# pioneer_2-bluepill_eletronic_wrapper-sup.net
KiCad netlist of a schematic drawn in Altium Designer
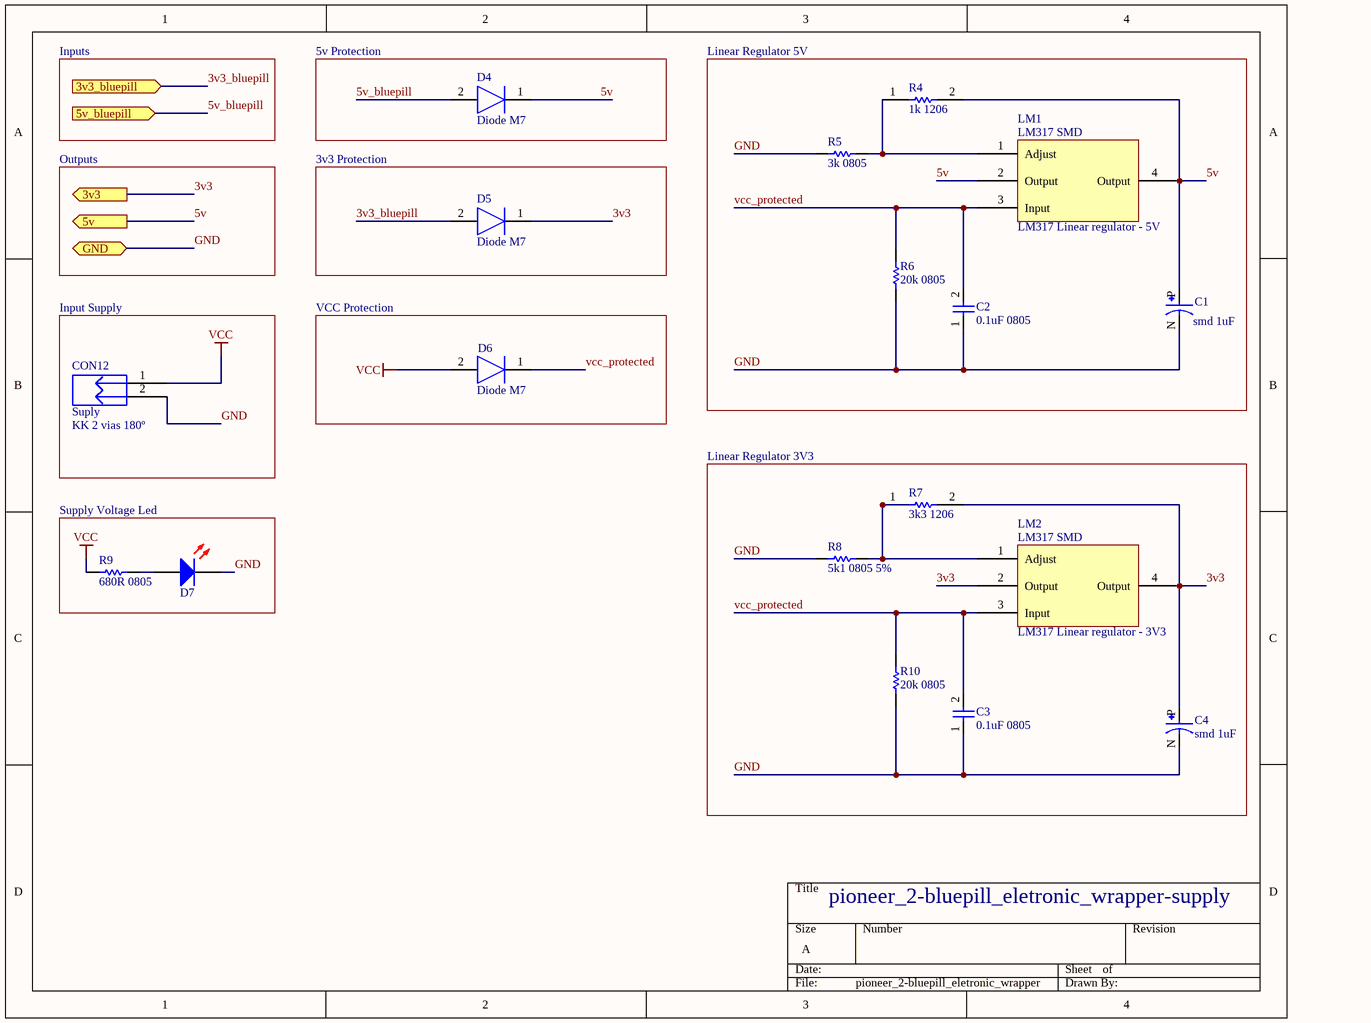
[diagram p0: pioneer_2-bluepill_eletronic_wrapper-supply.SchDoc]

(export (version "E")
  (design (tool "Eeschema 10.0.6"))
  (components
    (comp (ref "C1")
      (value "smd 1uF")
      (footprint "CAP_EEE1HA2R2SR")
      (description "Aluminum Organic Polymer Capacitors smd 50volts 1uF")
      (fields
        (field (name "MANUFACTURER_PART_NUMBER") "16SEPC470M")
        (field (name "MOUSER PART NUMBER") "667-16SEPC470M")
      )
      (libsource (lib "pioneer_2-bluepill_eletronic_wrapper") (part "Cap. Elet. smd 1uF 50V"))
    )
    (comp (ref "C2")
      (value "0.1uF 0805")
      (footprint "CAPACITOR 0805")
      (description "capacitor 0805")
      (fields
        (field (name "MANUFACTURER") "PANASONIC ELECTRONIC COMPONENTS")
        (field (name "MANUFACTURER PART NUMBER") "ERJ-3GEY0R00V")
      )
      (libsource (lib "pioneer_2-bluepill_eletronic_wrapper") (part "CAP 0805"))
    )
    (comp (ref "C3")
      (value "0.1uF 0805")
      (footprint "CAPACITOR 0805")
      (description "capacitor 0805")
      (fields
        (field (name "MANUFACTURER") "PANASONIC ELECTRONIC COMPONENTS")
        (field (name "MANUFACTURER PART NUMBER") "ERJ-3GEY0R00V")
      )
      (libsource (lib "pioneer_2-bluepill_eletronic_wrapper") (part "CAP 0805"))
    )
    (comp (ref "C4")
      (value "smd 1uF")
      (footprint "CAP_EEE1HA2R2SR")
      (description "Aluminum Organic Polymer Capacitors smd 50volts 1uF")
      (fields
        (field (name "MANUFACTURER_PART_NUMBER") "16SEPC470M")
        (field (name "MOUSER PART NUMBER") "667-16SEPC470M")
      )
      (libsource (lib "pioneer_2-bluepill_eletronic_wrapper") (part "Cap. Elet. smd 1uF 50V"))
    )
    (comp (ref "CON12")
      (value "Suply")
      (footprint "KK_2VIAS_180º")
      (description "Conector KK 2.54mm 2 vias")
      (fields (field (name "VALOR") "KK 2 vias 180º"))
      (libsource (lib "pioneer_2-bluepill_eletronic_wrapper") (part "KK_2.54_2vias"))
    )
    (comp (ref "D4")
      (value "Diode M7")
      (footprint "DIOM505270X240")
      (description "Diode, SMA, 1000V, 1A, 150°C")
      (fields (field (name "MF") "Diotec Semiconductor") (field (name "MP") "M7"))
      (libsource (lib "pioneer_2-bluepill_eletronic_wrapper") (part "Diode M7"))
    )
    (comp (ref "D5")
      (value "Diode M7")
      (footprint "DIOM505270X240")
      (description "Diode, SMA, 1000V, 1A, 150°C")
      (fields (field (name "MF") "Diotec Semiconductor") (field (name "MP") "M7"))
      (libsource (lib "pioneer_2-bluepill_eletronic_wrapper") (part "Diode M7"))
    )
    (comp (ref "D6")
      (value "Diode M7")
      (footprint "DIOM505270X240")
      (description "Diode, SMA, 1000V, 1A, 150°C")
      (fields (field (name "MF") "Diotec Semiconductor") (field (name "MP") "M7"))
      (libsource (lib "pioneer_2-bluepill_eletronic_wrapper") (part "Diode M7"))
    )
    (comp (ref "D7")
      (value "LED 3MM RED")
      (footprint "LED RED")
      (fields (field (name "MANUFACTURER") "Paralight") (field (name "MANUFACTURER PART NUMBER") "IMP585"))
      (libsource (lib "pioneer_2-bluepill_eletronic_wrapper") (part "LED 3MM RED"))
    )
    (comp (ref "LM1")
      (value "LM317 Linear regulator - 5V")
      (footprint "SOT-223-2")
      (description "SOT223")
      (libsource (lib "pioneer_2-bluepill_eletronic_wrapper") (part "lm317 smd"))
    )
    (comp (ref "LM2")
      (value "LM317 Linear regulator - 3V3")
      (footprint "SOT-223-2")
      (description "SOT223")
      (libsource (lib "pioneer_2-bluepill_eletronic_wrapper") (part "lm317 smd"))
    )
    (comp (ref "R4")
      (value "1k 1206")
      (footprint "RESC3216X60N")
      (description "RES 1206 5%")
      (fields
        (field (name "MANUFACTURER_PART_NUMBER") "CRCW12064K70FKEA")
        (field (name "MOUSER PART NUMBER") "71-CRCW1206-4.7K-E3")
      )
      (libsource (lib "pioneer_2-bluepill_eletronic_wrapper") (part "RES 1206"))
    )
    (comp (ref "R5")
      (value "3k 0805")
      (footprint "RESISTOR 0805")
      (description "0805")
      (fields
        (field (name "MANUFACTURER") "PANASONIC ELECTRONIC COMPONENTS")
        (field (name "MANUFACTURER PART NUMBER") "ERJ-3GEY0R00V")
      )
      (libsource (lib "pioneer_2-bluepill_eletronic_wrapper") (part "RES 0805 5%"))
    )
    (comp (ref "R6")
      (value "20k 0805")
      (footprint "RESISTOR 0805")
      (description "0805")
      (fields
        (field (name "MANUFACTURER") "PANASONIC ELECTRONIC COMPONENTS")
        (field (name "MANUFACTURER PART NUMBER") "ERJ-3GEY0R00V")
      )
      (libsource (lib "pioneer_2-bluepill_eletronic_wrapper") (part "RES 0805 5%"))
    )
    (comp (ref "R7")
      (value "3k3 1206")
      (footprint "RESC3216X60N")
      (description "RES 1206 5%")
      (fields
        (field (name "MANUFACTURER_PART_NUMBER") "CRCW12064K70FKEA")
        (field (name "MOUSER PART NUMBER") "71-CRCW1206-4.7K-E3")
      )
      (libsource (lib "pioneer_2-bluepill_eletronic_wrapper") (part "RES 1206"))
    )
    (comp (ref "R8")
      (value "5k1 0805 5%")
      (footprint "RESISTOR 0805")
      (description "0805")
      (fields
        (field (name "MANUFACTURER") "PANASONIC ELECTRONIC COMPONENTS")
        (field (name "MANUFACTURER PART NUMBER") "ERJ-3GEY0R00V")
      )
      (libsource (lib "pioneer_2-bluepill_eletronic_wrapper") (part "RES 0805 5%"))
    )
    (comp (ref "R9")
      (value "680R 0805")
      (footprint "RESISTOR 0805")
      (description "0805")
      (fields
        (field (name "MANUFACTURER") "PANASONIC ELECTRONIC COMPONENTS")
        (field (name "MANUFACTURER PART NUMBER") "ERJ-3GEY0R00V")
      )
      (libsource (lib "pioneer_2-bluepill_eletronic_wrapper") (part "RES 0805 5%"))
    )
    (comp (ref "R10")
      (value "20k 0805")
      (footprint "RESISTOR 0805")
      (description "0805")
      (fields
        (field (name "MANUFACTURER") "PANASONIC ELECTRONIC COMPONENTS")
        (field (name "MANUFACTURER PART NUMBER") "ERJ-3GEY0R00V")
      )
      (libsource (lib "pioneer_2-bluepill_eletronic_wrapper") (part "RES 0805 5%"))
    )
  )
  (nets
    (net (code "1") (name "/3v3") (class "Default")
      (node (ref "C4") (pin "P") (pinfunction "P_P") (pintype "passive"))
      (node (ref "D5") (pin "1") (pinfunction "K_1") (pintype "passive"))
      (node (ref "LM2") (pin "2") (pinfunction "Output_2") (pintype "passive"))
      (node (ref "LM2") (pin "4") (pinfunction "Output_4") (pintype "passive"))
      (node (ref "R7") (pin "2") (pinfunction "2_2") (pintype "passive"))
    )
    (net (code "2") (name "/3v3_bluepill") (class "Default")
      (node (ref "D5") (pin "2") (pinfunction "A_2") (pintype "passive"))
    )
    (net (code "3") (name "/5v") (class "Default")
      (node (ref "C1") (pin "P") (pinfunction "P_P") (pintype "passive"))
      (node (ref "D4") (pin "1") (pinfunction "K_1") (pintype "passive"))
      (node (ref "LM1") (pin "2") (pinfunction "Output_2") (pintype "passive"))
      (node (ref "LM1") (pin "4") (pinfunction "Output_4") (pintype "passive"))
      (node (ref "R4") (pin "2") (pinfunction "2_2") (pintype "passive"))
    )
    (net (code "4") (name "/5v_bluepill") (class "Default")
      (node (ref "D4") (pin "2") (pinfunction "A_2") (pintype "passive"))
    )
    (net (code "5") (name "/GND") (class "Default")
      (node (ref "C1") (pin "N") (pinfunction "N_N") (pintype "passive"))
      (node (ref "C2") (pin "1") (pinfunction "1_1") (pintype "passive"))
      (node (ref "C3") (pin "1") (pinfunction "1_1") (pintype "passive"))
      (node (ref "C4") (pin "N") (pinfunction "N_N") (pintype "passive"))
      (node (ref "CON12") (pin "2") (pintype "passive"))
      (node (ref "D7") (pin "2") (pinfunction "K_2") (pintype "passive"))
      (node (ref "R10") (pin "2") (pinfunction "2_2") (pintype "passive"))
      (node (ref "R5") (pin "2") (pinfunction "2_2") (pintype "passive"))
      (node (ref "R6") (pin "2") (pinfunction "2_2") (pintype "passive"))
      (node (ref "R8") (pin "1") (pinfunction "1_1") (pintype "passive"))
    )
    (net (code "6") (name "/vcc_protected") (class "Default")
      (node (ref "C2") (pin "2") (pinfunction "2_2") (pintype "passive"))
      (node (ref "C3") (pin "2") (pinfunction "2_2") (pintype "passive"))
      (node (ref "D6") (pin "1") (pinfunction "K_1") (pintype "passive"))
      (node (ref "LM1") (pin "3") (pinfunction "Input_3") (pintype "passive"))
      (node (ref "LM2") (pin "3") (pinfunction "Input_3") (pintype "passive"))
      (node (ref "R10") (pin "1") (pinfunction "1_1") (pintype "passive"))
      (node (ref "R6") (pin "1") (pinfunction "1_1") (pintype "passive"))
    )
    (net (code "7") (name "Net-(D7-A)") (class "Default")
      (node (ref "D7") (pin "1") (pinfunction "A_1") (pintype "passive"))
      (node (ref "R9") (pin "1") (pinfunction "1_1") (pintype "passive"))
    )
    (net (code "8") (name "Net-(LM1-Adjust)") (class "Default")
      (node (ref "LM1") (pin "1") (pinfunction "Adjust_1") (pintype "passive"))
      (node (ref "R4") (pin "1") (pinfunction "1_1") (pintype "passive"))
      (node (ref "R5") (pin "1") (pinfunction "1_1") (pintype "passive"))
    )
    (net (code "9") (name "Net-(LM2-Adjust)") (class "Default")
      (node (ref "LM2") (pin "1") (pinfunction "Adjust_1") (pintype "passive"))
      (node (ref "R7") (pin "1") (pinfunction "1_1") (pintype "passive"))
      (node (ref "R8") (pin "2") (pinfunction "2_2") (pintype "passive"))
    )
    (net (code "10") (name "VCC") (class "Default")
      (node (ref "CON12") (pin "1") (pintype "passive"))
      (node (ref "D6") (pin "2") (pinfunction "A_2") (pintype "passive"))
      (node (ref "R9") (pin "2") (pinfunction "2_2") (pintype "passive"))
    )
  )
)
